# dp_tsc-v21.net
KiCad netlist of a schematic drawn in EAGLE
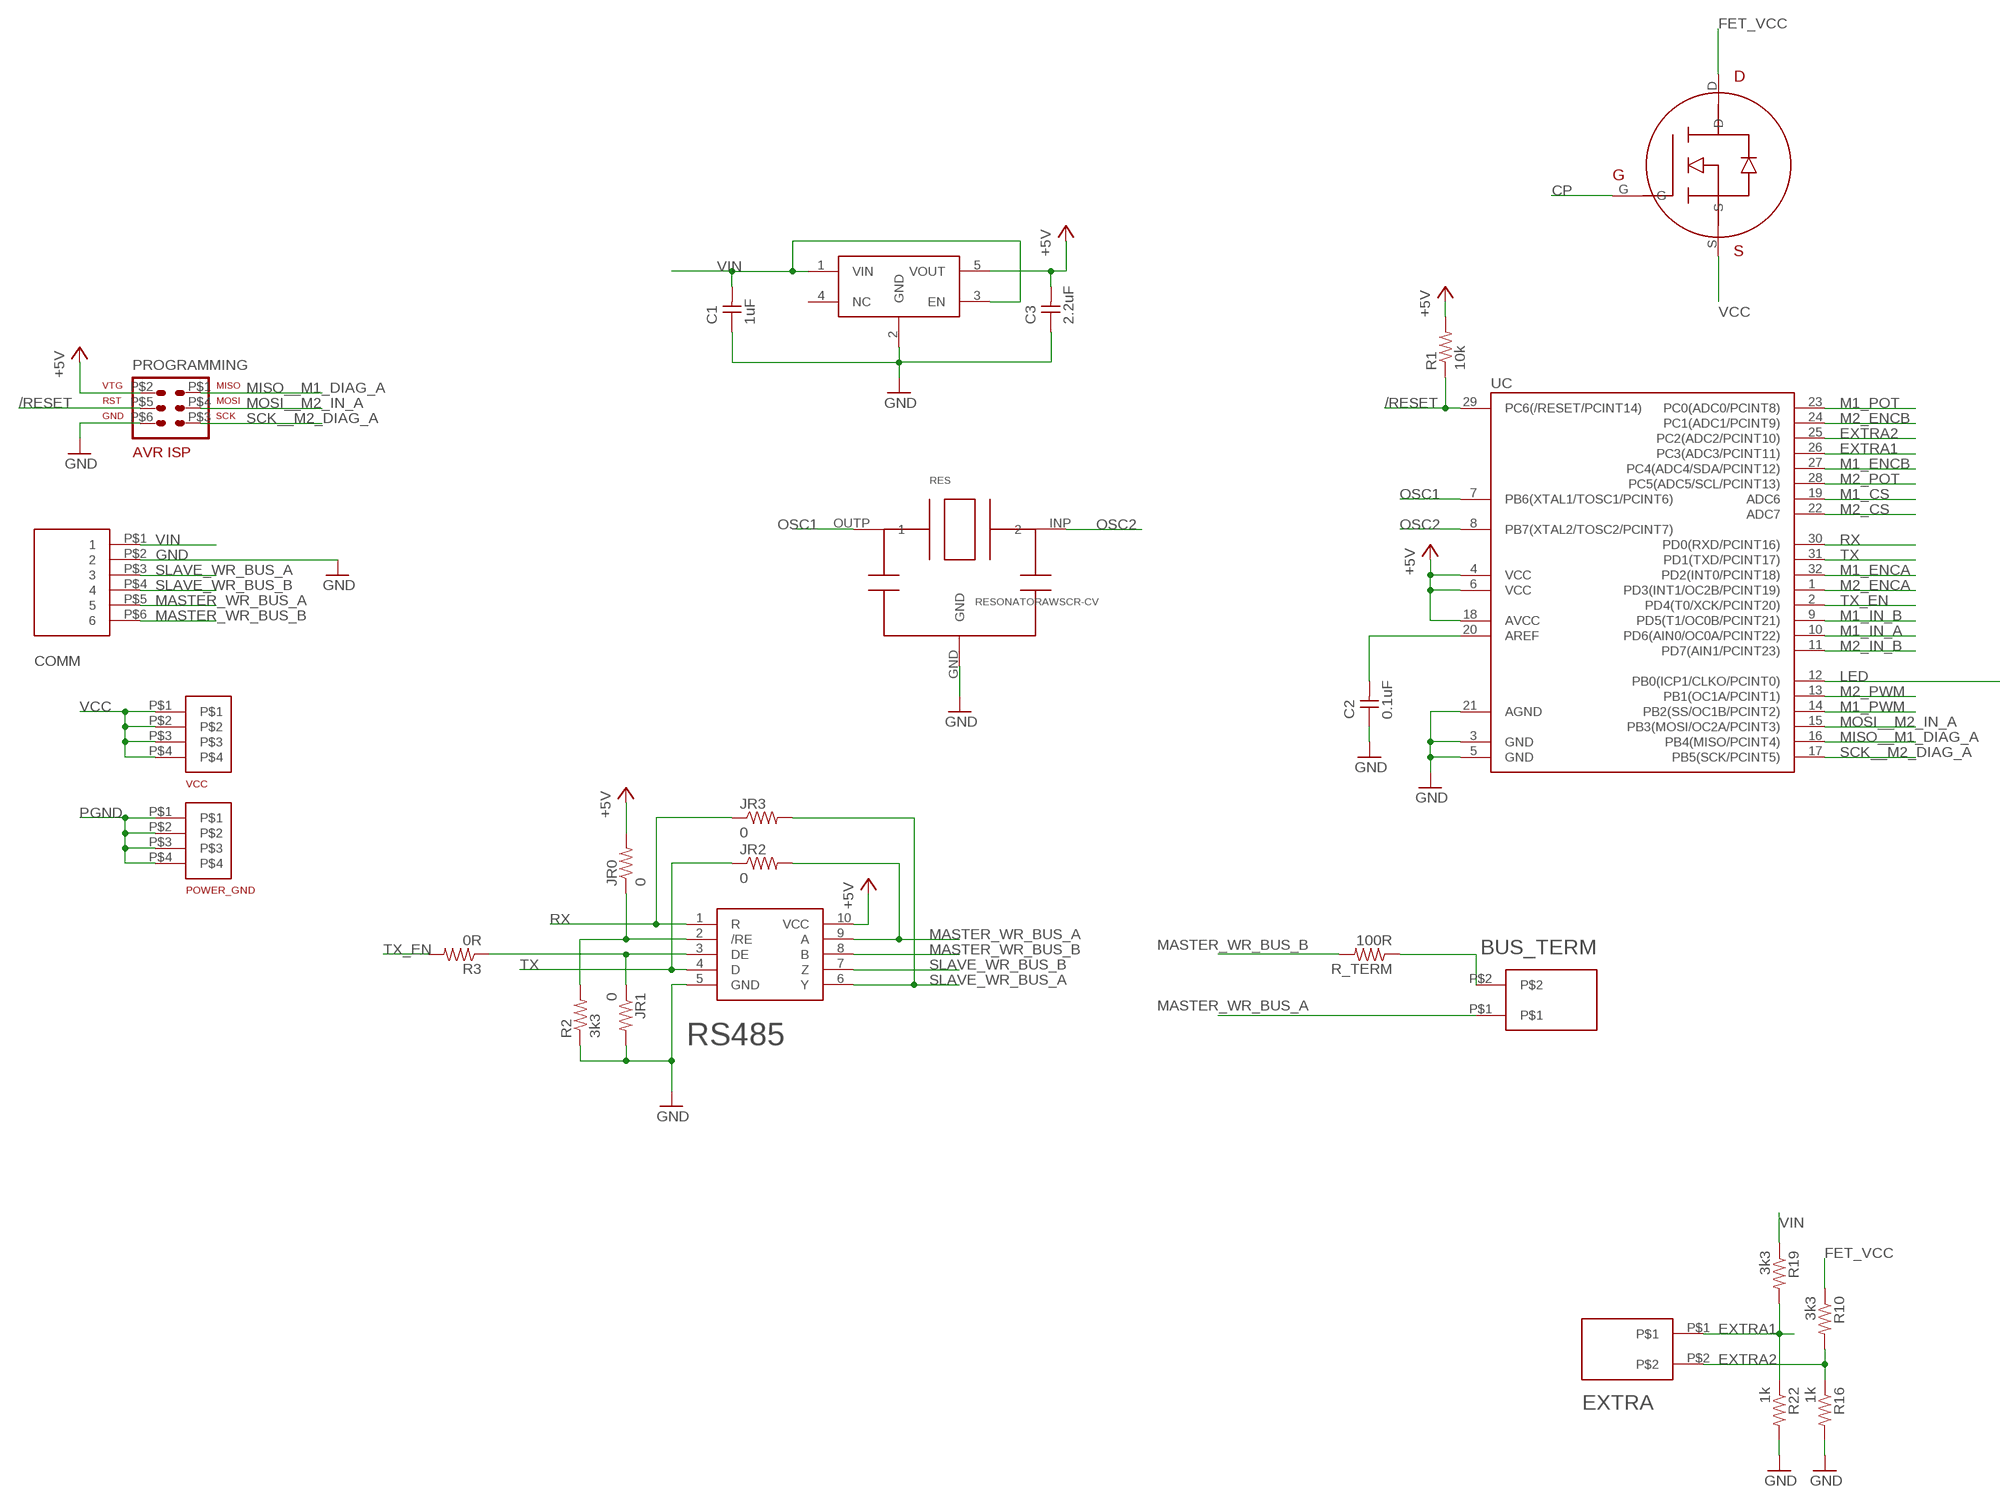
[diagram p0: schematic, sheet 1, part 1 of 2]
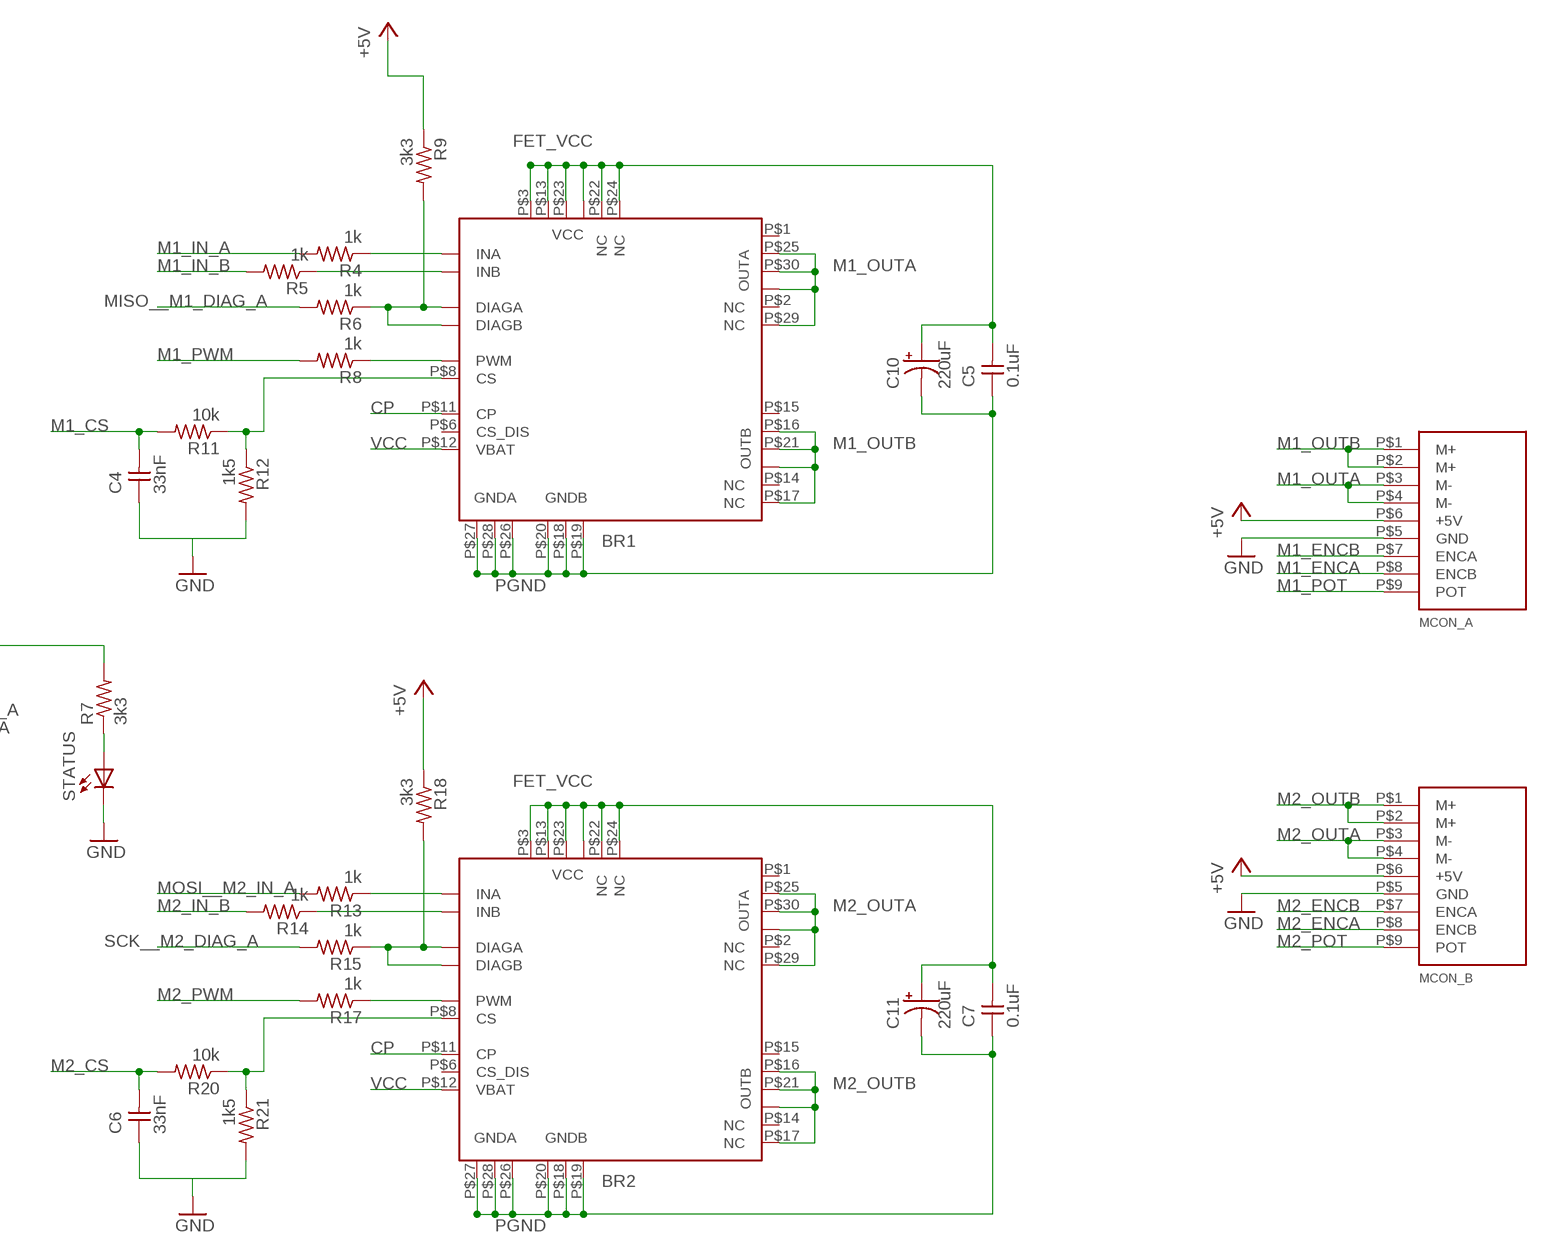
[diagram p1: schematic, sheet 1, part 2 of 2]

(export (version "E")
  (design (tool "Eeschema 10.0.6"))
  (components
    (comp (ref "BR1")
      (value "VNH5019A-E")
      (footprint "eagle-import:MULTIPOWERSO-30-SIGGI")
      (libsource (lib "eagle-import") (part "VNH5019A-E"))
    )
    (comp (ref "BR2")
      (value "VNH5019A-E")
      (footprint "eagle-import:MULTIPOWERSO-30-SIGGI")
      (libsource (lib "eagle-import") (part "VNH5019A-E"))
    )
    (comp (ref "BUS_TERM")
      (value "2PIN-100MILL")
      (footprint "eagle-import:2-PIN-100MIL")
      (libsource (lib "eagle-import") (part "2PIN-100MILL"))
    )
    (comp (ref "C1")
      (value "1uF")
      (footprint "eagle-import:0603")
      (libsource (lib "eagle-import") (part "CAPACITOR0603"))
    )
    (comp (ref "C2")
      (value "0.1uF")
      (footprint "eagle-import:0603")
      (libsource (lib "eagle-import") (part "CAPACITOR0603"))
    )
    (comp (ref "C3")
      (value "2.2uF")
      (footprint "eagle-import:0603")
      (libsource (lib "eagle-import") (part "CAPACITOR0603"))
    )
    (comp (ref "C4")
      (value "33nF")
      (footprint "eagle-import:0603")
      (libsource (lib "eagle-import") (part "CAPACITOR0603"))
    )
    (comp (ref "C5")
      (value "0.1uF")
      (footprint "eagle-import:0603")
      (libsource (lib "eagle-import") (part "CAPACITOR0603"))
    )
    (comp (ref "C6")
      (value "33nF")
      (footprint "eagle-import:0603")
      (libsource (lib "eagle-import") (part "CAPACITOR0603"))
    )
    (comp (ref "C7")
      (value "0.1uF")
      (footprint "eagle-import:0603")
      (libsource (lib "eagle-import") (part "CAPACITOR0603"))
    )
    (comp (ref "C10")
      (value "220uF")
      (footprint "eagle-import:HAO")
      (libsource (lib "eagle-import") (part "CAP-EMVY350ADA221MHA0G"))
    )
    (comp (ref "C11")
      (value "220uF")
      (footprint "eagle-import:HAO")
      (libsource (lib "eagle-import") (part "CAP-EMVY350ADA221MHA0G"))
    )
    (comp (ref "COMM")
      (value "6PIN-RIBBONCABLE-BOARDHEADER")
      (footprint "eagle-import:6PIN-HEADER-DUALROW")
      (libsource (lib "eagle-import") (part "6PIN-RIBBONCABLE-BOARDHEADER"))
    )
    (comp (ref "EXTRA")
      (value "2PIN-100MILL")
      (footprint "eagle-import:2-PIN-100MIL")
      (libsource (lib "eagle-import") (part "2PIN-100MILL"))
    )
    (comp (ref "FET")
      (value "MOSFET-N-FDD8896")
      (footprint "eagle-import:TO-252")
      (libsource (lib "eagle-import") (part "MOSFET-N-FDD8896"))
    )
    (comp (ref "JR0")
      (value "0")
      (footprint "eagle-import:0603")
      (libsource (lib "eagle-import") (part "RESISTOR0603"))
    )
    (comp (ref "JR1")
      (value "0")
      (footprint "eagle-import:0603")
      (libsource (lib "eagle-import") (part "RESISTOR0603"))
    )
    (comp (ref "JR2")
      (value "0")
      (footprint "eagle-import:0603")
      (libsource (lib "eagle-import") (part "RESISTOR0603"))
    )
    (comp (ref "JR3")
      (value "0")
      (footprint "eagle-import:0603")
      (libsource (lib "eagle-import") (part "RESISTOR0603"))
    )
    (comp (ref "MCON_A")
      (value "9-PIN-MOTOR_CONNECTOR")
      (footprint "eagle-import:9-PIN-2.54MM-TERMINAL-BLOCK")
      (libsource (lib "eagle-import") (part "9-PIN-MOTOR_CONNECTOR"))
    )
    (comp (ref "MCON_B")
      (value "9-PIN-MOTOR_CONNECTOR")
      (footprint "eagle-import:9-PIN-2.54MM-TERMINAL-BLOCK")
      (libsource (lib "eagle-import") (part "9-PIN-MOTOR_CONNECTOR"))
    )
    (comp (ref "POWER_GND")
      (value "SCREW_TERMINAL_7700K")
      (footprint "eagle-import:SCREW_TERM_7700K")
      (libsource (lib "eagle-import") (part "SCREW_TERMINAL_7700K"))
    )
    (comp (ref "PROGRAMMING")
      (value "AVR-ISP-6SURFACE_MOUNT")
      (footprint "eagle-import:SMD6")
      (libsource (lib "eagle-import") (part "AVR-ISP-6SURFACE_MOUNT"))
    )
    (comp (ref "R1")
      (value "10k")
      (footprint "eagle-import:0603")
      (libsource (lib "eagle-import") (part "RESISTOR0603"))
    )
    (comp (ref "R2")
      (value "3k3")
      (footprint "eagle-import:0603")
      (libsource (lib "eagle-import") (part "RESISTOR0603"))
    )
    (comp (ref "R3")
      (value "0R")
      (footprint "eagle-import:0603")
      (libsource (lib "eagle-import") (part "RESISTOR0603"))
    )
    (comp (ref "R4")
      (value "1k")
      (footprint "eagle-import:0603")
      (libsource (lib "eagle-import") (part "RESISTOR0603"))
    )
    (comp (ref "R5")
      (value "1k")
      (footprint "eagle-import:0603")
      (libsource (lib "eagle-import") (part "RESISTOR0603"))
    )
    (comp (ref "R6")
      (value "1k")
      (footprint "eagle-import:0603")
      (libsource (lib "eagle-import") (part "RESISTOR0603"))
    )
    (comp (ref "R7")
      (value "3k3")
      (footprint "eagle-import:0603")
      (libsource (lib "eagle-import") (part "RESISTOR0603"))
    )
    (comp (ref "R8")
      (value "1k")
      (footprint "eagle-import:0603")
      (libsource (lib "eagle-import") (part "RESISTOR0603"))
    )
    (comp (ref "R9")
      (value "3k3")
      (footprint "eagle-import:0603")
      (libsource (lib "eagle-import") (part "RESISTOR0603"))
    )
    (comp (ref "R10")
      (value "3k3")
      (footprint "eagle-import:0603")
      (libsource (lib "eagle-import") (part "RESISTOR0603"))
    )
    (comp (ref "R11")
      (value "10k")
      (footprint "eagle-import:0603")
      (libsource (lib "eagle-import") (part "RESISTOR0603"))
    )
    (comp (ref "R12")
      (value "1k5")
      (footprint "eagle-import:0603")
      (libsource (lib "eagle-import") (part "RESISTOR0603"))
    )
    (comp (ref "R13")
      (value "1k")
      (footprint "eagle-import:0603")
      (libsource (lib "eagle-import") (part "RESISTOR0603"))
    )
    (comp (ref "R14")
      (value "1k")
      (footprint "eagle-import:0603")
      (libsource (lib "eagle-import") (part "RESISTOR0603"))
    )
    (comp (ref "R15")
      (value "1k")
      (footprint "eagle-import:0603")
      (libsource (lib "eagle-import") (part "RESISTOR0603"))
    )
    (comp (ref "R16")
      (value "1k")
      (footprint "eagle-import:0603")
      (libsource (lib "eagle-import") (part "RESISTOR0603"))
    )
    (comp (ref "R17")
      (value "1k")
      (footprint "eagle-import:0603")
      (libsource (lib "eagle-import") (part "RESISTOR0603"))
    )
    (comp (ref "R18")
      (value "3k3")
      (footprint "eagle-import:0603")
      (libsource (lib "eagle-import") (part "RESISTOR0603"))
    )
    (comp (ref "R19")
      (value "3k3")
      (footprint "eagle-import:0603")
      (libsource (lib "eagle-import") (part "RESISTOR0603"))
    )
    (comp (ref "R20")
      (value "10k")
      (footprint "eagle-import:0603")
      (libsource (lib "eagle-import") (part "RESISTOR0603"))
    )
    (comp (ref "R21")
      (value "1k5")
      (footprint "eagle-import:0603")
      (libsource (lib "eagle-import") (part "RESISTOR0603"))
    )
    (comp (ref "R22")
      (value "1k")
      (footprint "eagle-import:0603")
      (libsource (lib "eagle-import") (part "RESISTOR0603"))
    )
    (comp (ref "RES")
      (value "RESONATORAWSCR-CV")
      (footprint "eagle-import:AWSCR-CV")
      (libsource (lib "eagle-import") (part "RESONATORAWSCR-CV"))
    )
    (comp (ref "RS485")
      (value "RS485-SN65HVD3086EDGSR")
      (footprint "eagle-import:MSOP-10")
      (libsource (lib "eagle-import") (part "RS485-SN65HVD3086EDGSR"))
    )
    (comp (ref "R_TERM")
      (value "100R")
      (footprint "eagle-import:0603")
      (libsource (lib "eagle-import") (part "RESISTOR0603"))
    )
    (comp (ref "STATUS")
      (value "LED1206")
      (footprint "eagle-import:CHIPLED_1206")
      (libsource (lib "eagle-import") (part "LED1206"))
    )
    (comp (ref "UC")
      (value "MEGA48/88/168-AU")
      (footprint "eagle-import:TQFP32-08")
      (libsource (lib "eagle-import") (part "MEGA48/88/168-AU"))
    )
    (comp (ref "VCC")
      (value "SCREW_TERMINAL_7700K")
      (footprint "eagle-import:SCREW_TERM_7700K")
      (libsource (lib "eagle-import") (part "SCREW_TERMINAL_7700K"))
    )
    (comp (ref "VREG")
      (value "MIC5235")
      (footprint "eagle-import:SOT-23-5")
      (libsource (lib "eagle-import") (part "MIC5235"))
    )
  )
  (nets
    (net (code "1") (name "+5V") (class "Default")
      (node (ref "C3") (pin "2") (pinfunction "2_2") (pintype "passive"))
      (node (ref "JR0") (pin "2") (pinfunction "2_2") (pintype "passive"))
      (node (ref "MCON_A") (pin "P$6") (pinfunction "+5V_P$6") (pintype "bidirectional"))
      (node (ref "MCON_B") (pin "P$6") (pinfunction "+5V_P$6") (pintype "bidirectional"))
      (node (ref "PROGRAMMING") (pin "P$2") (pinfunction "2_P$2") (pintype "passive"))
      (node (ref "R1") (pin "2") (pinfunction "2_2") (pintype "passive"))
      (node (ref "R18") (pin "1") (pinfunction "1_1") (pintype "passive"))
      (node (ref "R9") (pin "1") (pinfunction "1_1") (pintype "passive"))
      (node (ref "RS485") (pin "10") (pinfunction "VCC_10") (pintype "bidirectional"))
      (node (ref "UC") (pin "18") (pinfunction "AVCC_18") (pintype "passive"))
      (node (ref "UC") (pin "4") (pinfunction "VCC_4") (pintype "power_in"))
      (node (ref "UC") (pin "6") (pinfunction "VCC_6") (pintype "power_in"))
      (node (ref "VREG") (pin "5") (pinfunction "VOUT_5") (pintype "bidirectional"))
    )
    (net (code "2") (name "/CP") (class "Default")
      (node (ref "BR1") (pin "P$11") (pinfunction "CP_P$11") (pintype "bidirectional"))
      (node (ref "BR2") (pin "P$11") (pinfunction "CP_P$11") (pintype "bidirectional"))
      (node (ref "FET") (pin "G") (pinfunction "G_G") (pintype "bidirectional"))
    )
    (net (code "3") (name "/EXTRA1") (class "Default")
      (node (ref "EXTRA") (pin "P$1") (pinfunction "P$1_P$1") (pintype "bidirectional"))
      (node (ref "R19") (pin "2") (pinfunction "2_2") (pintype "passive"))
      (node (ref "R22") (pin "1") (pinfunction "1_1") (pintype "passive"))
      (node (ref "UC") (pin "26") (pinfunction "PC3(ADC3/PCINT11)_26") (pintype "bidirectional"))
    )
    (net (code "4") (name "/EXTRA2") (class "Default")
      (node (ref "EXTRA") (pin "P$2") (pinfunction "P$2_P$2") (pintype "bidirectional"))
      (node (ref "R10") (pin "2") (pinfunction "2_2") (pintype "passive"))
      (node (ref "R16") (pin "1") (pinfunction "1_1") (pintype "passive"))
      (node (ref "UC") (pin "25") (pinfunction "PC2(ADC2/PCINT10)_25") (pintype "bidirectional"))
    )
    (net (code "5") (name "/FET_VCC") (class "Default")
      (node (ref "BR1") (pin "P$13") (pinfunction "VCC_P$13") (pintype "power_in"))
      (node (ref "BR1") (pin "P$22") (pinfunction "NC_P$22") (pintype "bidirectional"))
      (node (ref "BR1") (pin "P$23") (pinfunction "VCC_P$23") (pintype "power_in"))
      (node (ref "BR1") (pin "P$24") (pinfunction "NC_P$24") (pintype "bidirectional"))
      (node (ref "BR1") (pin "P$3") (pinfunction "VCC_P$3") (pintype "power_in"))
      (node (ref "BR1") (pin "VCC_SLUG") (pinfunction "VCC_VCC_SLUG") (pintype "power_in"))
      (node (ref "BR2") (pin "P$13") (pinfunction "VCC_P$13") (pintype "power_in"))
      (node (ref "BR2") (pin "P$22") (pinfunction "NC_P$22") (pintype "bidirectional"))
      (node (ref "BR2") (pin "P$23") (pinfunction "VCC_P$23") (pintype "power_in"))
      (node (ref "BR2") (pin "P$24") (pinfunction "NC_P$24") (pintype "bidirectional"))
      (node (ref "BR2") (pin "P$3") (pinfunction "VCC_P$3") (pintype "power_in"))
      (node (ref "BR2") (pin "VCC_SLUG") (pinfunction "VCC_VCC_SLUG") (pintype "power_in"))
      (node (ref "C10") (pin "+") (pinfunction "+_+") (pintype "passive"))
      (node (ref "C11") (pin "+") (pinfunction "+_+") (pintype "passive"))
      (node (ref "C5") (pin "2") (pinfunction "2_2") (pintype "passive"))
      (node (ref "C7") (pin "2") (pinfunction "2_2") (pintype "passive"))
      (node (ref "FET") (pin "D") (pinfunction "D_D") (pintype "bidirectional"))
      (node (ref "R10") (pin "1") (pinfunction "1_1") (pintype "passive"))
    )
    (net (code "6") (name "/LED") (class "Default")
      (node (ref "R7") (pin "2") (pinfunction "2_2") (pintype "passive"))
      (node (ref "UC") (pin "12") (pinfunction "PB0(ICP1/CLKO/PCINT0)_12") (pintype "bidirectional"))
    )
    (net (code "7") (name "/M1_CS") (class "Default")
      (node (ref "C4") (pin "2") (pinfunction "2_2") (pintype "passive"))
      (node (ref "R11") (pin "2") (pinfunction "2_2") (pintype "passive"))
      (node (ref "UC") (pin "19") (pinfunction "ADC6_19") (pintype "passive"))
    )
    (net (code "8") (name "/M1_ENCA") (class "Default")
      (node (ref "MCON_A") (pin "P$8") (pinfunction "ENCB_P$8") (pintype "bidirectional"))
      (node (ref "UC") (pin "32") (pinfunction "PD2(INT0/PCINT18)_32") (pintype "bidirectional"))
    )
    (net (code "9") (name "/M1_ENCB") (class "Default")
      (node (ref "MCON_A") (pin "P$7") (pinfunction "ENCA_P$7") (pintype "bidirectional"))
      (node (ref "UC") (pin "27") (pinfunction "PC4(ADC4/SDA/PCINT12)_27") (pintype "bidirectional"))
    )
    (net (code "10") (name "/M1_IN_A") (class "Default")
      (node (ref "R4") (pin "2") (pinfunction "2_2") (pintype "passive"))
      (node (ref "UC") (pin "10") (pinfunction "PD6(AIN0/OC0A/PCINT22)_10") (pintype "bidirectional"))
    )
    (net (code "11") (name "/M1_IN_B") (class "Default")
      (node (ref "R5") (pin "2") (pinfunction "2_2") (pintype "passive"))
      (node (ref "UC") (pin "9") (pinfunction "PD5(T1/OC0B/PCINT21)_9") (pintype "bidirectional"))
    )
    (net (code "12") (name "/M1_OUTA") (class "Default")
      (node (ref "BR1") (pin "OUTA_SLUG") (pinfunction "OUTA_OUTA_SLUG") (pintype "passive"))
      (node (ref "BR1") (pin "P$25") (pinfunction "OUTA_P$25") (pintype "passive"))
      (node (ref "BR1") (pin "P$29") (pinfunction "NC_P$29") (pintype "bidirectional"))
      (node (ref "BR1") (pin "P$30") (pinfunction "OUTA_P$30") (pintype "passive"))
      (node (ref "MCON_A") (pin "P$3") (pinfunction "M-_P$3") (pintype "bidirectional"))
      (node (ref "MCON_A") (pin "P$4") (pinfunction "M-_P$4") (pintype "bidirectional"))
    )
    (net (code "13") (name "/M1_OUTB") (class "Default")
      (node (ref "BR1") (pin "OUTB_SLUG") (pinfunction "OUTB_OUTB_SLUG") (pintype "passive"))
      (node (ref "BR1") (pin "P$16") (pinfunction "OUTB_P$16") (pintype "passive"))
      (node (ref "BR1") (pin "P$17") (pinfunction "NC_P$17") (pintype "bidirectional"))
      (node (ref "BR1") (pin "P$21") (pinfunction "OUTB_P$21") (pintype "passive"))
      (node (ref "MCON_A") (pin "P$1") (pinfunction "M+_P$1") (pintype "bidirectional"))
      (node (ref "MCON_A") (pin "P$2") (pinfunction "M+_P$2") (pintype "bidirectional"))
    )
    (net (code "14") (name "/M1_POT") (class "Default")
      (node (ref "MCON_A") (pin "P$9") (pinfunction "POT_P$9") (pintype "bidirectional"))
      (node (ref "UC") (pin "23") (pinfunction "PC0(ADC0/PCINT8)_23") (pintype "bidirectional"))
    )
    (net (code "15") (name "/M1_PWM") (class "Default")
      (node (ref "R8") (pin "2") (pinfunction "2_2") (pintype "passive"))
      (node (ref "UC") (pin "14") (pinfunction "PB2(SS/OC1B/PCINT2)_14") (pintype "bidirectional"))
    )
    (net (code "16") (name "/M2_CS") (class "Default")
      (node (ref "C6") (pin "2") (pinfunction "2_2") (pintype "passive"))
      (node (ref "R20") (pin "2") (pinfunction "2_2") (pintype "passive"))
      (node (ref "UC") (pin "22") (pinfunction "ADC7_22") (pintype "passive"))
    )
    (net (code "17") (name "/M2_ENCA") (class "Default")
      (node (ref "MCON_B") (pin "P$8") (pinfunction "ENCB_P$8") (pintype "bidirectional"))
      (node (ref "UC") (pin "1") (pinfunction "PD3(INT1/OC2B/PCINT19)_1") (pintype "bidirectional"))
    )
    (net (code "18") (name "/M2_ENCB") (class "Default")
      (node (ref "MCON_B") (pin "P$7") (pinfunction "ENCA_P$7") (pintype "bidirectional"))
      (node (ref "UC") (pin "24") (pinfunction "PC1(ADC1/PCINT9)_24") (pintype "bidirectional"))
    )
    (net (code "19") (name "/M2_IN_B") (class "Default")
      (node (ref "R14") (pin "2") (pinfunction "2_2") (pintype "passive"))
      (node (ref "UC") (pin "11") (pinfunction "PD7(AIN1/PCINT23)_11") (pintype "bidirectional"))
    )
    (net (code "20") (name "/M2_OUTA") (class "Default")
      (node (ref "BR2") (pin "OUTA_SLUG") (pinfunction "OUTA_OUTA_SLUG") (pintype "passive"))
      (node (ref "BR2") (pin "P$25") (pinfunction "OUTA_P$25") (pintype "passive"))
      (node (ref "BR2") (pin "P$29") (pinfunction "NC_P$29") (pintype "bidirectional"))
      (node (ref "BR2") (pin "P$30") (pinfunction "OUTA_P$30") (pintype "passive"))
      (node (ref "MCON_B") (pin "P$3") (pinfunction "M-_P$3") (pintype "bidirectional"))
      (node (ref "MCON_B") (pin "P$4") (pinfunction "M-_P$4") (pintype "bidirectional"))
    )
    (net (code "21") (name "/M2_OUTB") (class "Default")
      (node (ref "BR2") (pin "OUTB_SLUG") (pinfunction "OUTB_OUTB_SLUG") (pintype "passive"))
      (node (ref "BR2") (pin "P$16") (pinfunction "OUTB_P$16") (pintype "passive"))
      (node (ref "BR2") (pin "P$17") (pinfunction "NC_P$17") (pintype "bidirectional"))
      (node (ref "BR2") (pin "P$21") (pinfunction "OUTB_P$21") (pintype "passive"))
      (node (ref "MCON_B") (pin "P$1") (pinfunction "M+_P$1") (pintype "bidirectional"))
      (node (ref "MCON_B") (pin "P$2") (pinfunction "M+_P$2") (pintype "bidirectional"))
    )
    (net (code "22") (name "/M2_POT") (class "Default")
      (node (ref "MCON_B") (pin "P$9") (pinfunction "POT_P$9") (pintype "bidirectional"))
      (node (ref "UC") (pin "28") (pinfunction "PC5(ADC5/SCL/PCINT13)_28") (pintype "bidirectional"))
    )
    (net (code "23") (name "/M2_PWM") (class "Default")
      (node (ref "R17") (pin "2") (pinfunction "2_2") (pintype "passive"))
      (node (ref "UC") (pin "13") (pinfunction "PB1(OC1A/PCINT1)_13") (pintype "bidirectional"))
    )
    (net (code "24") (name "/MASTER_WR_BUS_A") (class "Default")
      (node (ref "BUS_TERM") (pin "P$1") (pinfunction "P$1_P$1") (pintype "bidirectional"))
      (node (ref "COMM") (pin "P$5") (pinfunction "5_P$5") (pintype "bidirectional"))
      (node (ref "JR2") (pin "2") (pinfunction "2_2") (pintype "passive"))
      (node (ref "RS485") (pin "9") (pinfunction "A_9") (pintype "bidirectional"))
    )
    (net (code "25") (name "/MASTER_WR_BUS_B") (class "Default")
      (node (ref "COMM") (pin "P$6") (pinfunction "6_P$6") (pintype "bidirectional"))
      (node (ref "RS485") (pin "8") (pinfunction "B_8") (pintype "bidirectional"))
      (node (ref "R_TERM") (pin "2") (pinfunction "2_2") (pintype "passive"))
    )
    (net (code "26") (name "/MISO__M1_DIAG_A") (class "Default")
      (node (ref "PROGRAMMING") (pin "P$1") (pinfunction "1_P$1") (pintype "passive"))
      (node (ref "R6") (pin "2") (pinfunction "2_2") (pintype "passive"))
      (node (ref "UC") (pin "16") (pinfunction "PB4(MISO/PCINT4)_16") (pintype "bidirectional"))
    )
    (net (code "27") (name "/MOSI__M2_IN_A") (class "Default")
      (node (ref "PROGRAMMING") (pin "P$4") (pinfunction "4_P$4") (pintype "passive"))
      (node (ref "R13") (pin "2") (pinfunction "2_2") (pintype "passive"))
      (node (ref "UC") (pin "15") (pinfunction "PB3(MOSI/OC2A/PCINT3)_15") (pintype "bidirectional"))
    )
    (net (code "28") (name "/OSC1") (class "Default")
      (node (ref "RES") (pin "OUTP") (pinfunction "1_OUTP") (pintype "bidirectional"))
      (node (ref "UC") (pin "7") (pinfunction "PB6(XTAL1/TOSC1/PCINT6)_7") (pintype "bidirectional"))
    )
    (net (code "29") (name "/OSC2") (class "Default")
      (node (ref "RES") (pin "INP") (pinfunction "2_INP") (pintype "bidirectional"))
      (node (ref "UC") (pin "8") (pinfunction "PB7(XTAL2/TOSC2/PCINT7)_8") (pintype "bidirectional"))
    )
    (net (code "30") (name "/PGND") (class "Default")
      (node (ref "BR1") (pin "P$18") (pinfunction "GNDB_P$18") (pintype "power_in"))
      (node (ref "BR1") (pin "P$19") (pinfunction "GNDB_P$19") (pintype "power_in"))
      (node (ref "BR1") (pin "P$20") (pinfunction "GNDB_P$20") (pintype "power_in"))
      (node (ref "BR1") (pin "P$26") (pinfunction "GNDA_P$26") (pintype "power_in"))
      (node (ref "BR1") (pin "P$27") (pinfunction "GNDA_P$27") (pintype "power_in"))
      (node (ref "BR1") (pin "P$28") (pinfunction "GNDA_P$28") (pintype "power_in"))
      (node (ref "BR2") (pin "P$18") (pinfunction "GNDB_P$18") (pintype "power_in"))
      (node (ref "BR2") (pin "P$19") (pinfunction "GNDB_P$19") (pintype "power_in"))
      (node (ref "BR2") (pin "P$20") (pinfunction "GNDB_P$20") (pintype "power_in"))
      (node (ref "BR2") (pin "P$26") (pinfunction "GNDA_P$26") (pintype "power_in"))
      (node (ref "BR2") (pin "P$27") (pinfunction "GNDA_P$27") (pintype "power_in"))
      (node (ref "BR2") (pin "P$28") (pinfunction "GNDA_P$28") (pintype "power_in"))
      (node (ref "C10") (pin "-") (pinfunction "-_-") (pintype "passive"))
      (node (ref "C11") (pin "-") (pinfunction "-_-") (pintype "passive"))
      (node (ref "C5") (pin "1") (pinfunction "1_1") (pintype "passive"))
      (node (ref "C7") (pin "1") (pinfunction "1_1") (pintype "passive"))
      (node (ref "POWER_GND") (pin "P$1") (pinfunction "P$1_P$1") (pintype "bidirectional"))
      (node (ref "POWER_GND") (pin "P$2") (pinfunction "P$2_P$2") (pintype "bidirectional"))
      (node (ref "POWER_GND") (pin "P$3") (pinfunction "P$3_P$3") (pintype "bidirectional"))
      (node (ref "POWER_GND") (pin "P$4") (pinfunction "P$4_P$4") (pintype "bidirectional"))
    )
    (net (code "31") (name "/RX") (class "Default")
      (node (ref "JR3") (pin "1") (pinfunction "1_1") (pintype "passive"))
      (node (ref "RS485") (pin "1") (pinfunction "R_1") (pintype "bidirectional"))
      (node (ref "UC") (pin "30") (pinfunction "PD0(RXD/PCINT16)_30") (pintype "bidirectional"))
    )
    (net (code "32") (name "/SCK__M2_DIAG_A") (class "Default")
      (node (ref "PROGRAMMING") (pin "P$3") (pinfunction "3_P$3") (pintype "passive"))
      (node (ref "R15") (pin "2") (pinfunction "2_2") (pintype "passive"))
      (node (ref "UC") (pin "17") (pinfunction "PB5(SCK/PCINT5)_17") (pintype "bidirectional"))
    )
    (net (code "33") (name "/SLAVE_WR_BUS_A") (class "Default")
      (node (ref "COMM") (pin "P$3") (pinfunction "3_P$3") (pintype "bidirectional"))
      (node (ref "JR3") (pin "2") (pinfunction "2_2") (pintype "passive"))
      (node (ref "RS485") (pin "6") (pinfunction "Y_6") (pintype "bidirectional"))
    )
    (net (code "34") (name "/SLAVE_WR_BUS_B") (class "Default")
      (node (ref "COMM") (pin "P$4") (pinfunction "4_P$4") (pintype "bidirectional"))
      (node (ref "RS485") (pin "7") (pinfunction "Z_7") (pintype "bidirectional"))
    )
    (net (code "35") (name "/TX") (class "Default")
      (node (ref "JR2") (pin "1") (pinfunction "1_1") (pintype "passive"))
      (node (ref "RS485") (pin "4") (pinfunction "D_4") (pintype "bidirectional"))
      (node (ref "UC") (pin "31") (pinfunction "PD1(TXD/PCINT17)_31") (pintype "bidirectional"))
    )
    (net (code "36") (name "/TX_EN") (class "Default")
      (node (ref "R3") (pin "2") (pinfunction "2_2") (pintype "passive"))
      (node (ref "UC") (pin "2") (pinfunction "PD4(T0/XCK/PCINT20)_2") (pintype "bidirectional"))
    )
    (net (code "37") (name "/VCC") (class "Default")
      (node (ref "BR1") (pin "P$12") (pinfunction "VBAT_P$12") (pintype "bidirectional"))
      (node (ref "BR2") (pin "P$12") (pinfunction "VBAT_P$12") (pintype "bidirectional"))
      (node (ref "FET") (pin "S") (pinfunction "S_S") (pintype "bidirectional"))
      (node (ref "VCC") (pin "P$1") (pinfunction "P$1_P$1") (pintype "bidirectional"))
      (node (ref "VCC") (pin "P$2") (pinfunction "P$2_P$2") (pintype "bidirectional"))
      (node (ref "VCC") (pin "P$3") (pinfunction "P$3_P$3") (pintype "bidirectional"))
      (node (ref "VCC") (pin "P$4") (pinfunction "P$4_P$4") (pintype "bidirectional"))
    )
    (net (code "38") (name "/VIN") (class "Default")
      (node (ref "C1") (pin "2") (pinfunction "2_2") (pintype "passive"))
      (node (ref "COMM") (pin "P$1") (pinfunction "1_P$1") (pintype "bidirectional"))
      (node (ref "R19") (pin "1") (pinfunction "1_1") (pintype "passive"))
      (node (ref "VREG") (pin "1") (pinfunction "VIN_1") (pintype "bidirectional"))
      (node (ref "VREG") (pin "3") (pinfunction "EN_3") (pintype "bidirectional"))
    )
    (net (code "39") (name "/{slash}RESET") (class "Default")
      (node (ref "PROGRAMMING") (pin "P$5") (pinfunction "5_P$5") (pintype "passive"))
      (node (ref "R1") (pin "1") (pinfunction "1_1") (pintype "passive"))
      (node (ref "UC") (pin "29") (pinfunction "PC6(/RESET/PCINT14)_29") (pintype "bidirectional"))
    )
    (net (code "40") (name "GND") (class "Default")
      (node (ref "C1") (pin "1") (pinfunction "1_1") (pintype "passive"))
      (node (ref "C2") (pin "1") (pinfunction "1_1") (pintype "passive"))
      (node (ref "C3") (pin "1") (pinfunction "1_1") (pintype "passive"))
      (node (ref "C4") (pin "1") (pinfunction "1_1") (pintype "passive"))
      (node (ref "C6") (pin "1") (pinfunction "1_1") (pintype "passive"))
      (node (ref "COMM") (pin "P$2") (pinfunction "2_P$2") (pintype "bidirectional"))
      (node (ref "JR1") (pin "2") (pinfunction "2_2") (pintype "passive"))
      (node (ref "MCON_A") (pin "P$5") (pinfunction "GND_P$5") (pintype "bidirectional"))
      (node (ref "MCON_B") (pin "P$5") (pinfunction "GND_P$5") (pintype "bidirectional"))
      (node (ref "PROGRAMMING") (pin "P$6") (pinfunction "6_P$6") (pintype "passive"))
      (node (ref "R12") (pin "2") (pinfunction "2_2") (pintype "passive"))
      (node (ref "R16") (pin "2") (pinfunction "2_2") (pintype "passive"))
      (node (ref "R2") (pin "1") (pinfunction "1_1") (pintype "passive"))
      (node (ref "R21") (pin "2") (pinfunction "2_2") (pintype "passive"))
      (node (ref "R22") (pin "2") (pinfunction "2_2") (pintype "passive"))
      (node (ref "RES") (pin "GND") (pinfunction "GND_GND") (pintype "bidirectional"))
      (node (ref "RS485") (pin "5") (pinfunction "GND_5") (pintype "bidirectional"))
      (node (ref "STATUS") (pin "C") (pinfunction "C_C") (pintype "passive"))
      (node (ref "UC") (pin "21") (pinfunction "AGND_21") (pintype "power_in"))
      (node (ref "UC") (pin "3") (pinfunction "GND_3") (pintype "power_in"))
      (node (ref "UC") (pin "5") (pinfunction "GND_5") (pintype "power_in"))
      (node (ref "VREG") (pin "2") (pinfunction "GND_2") (pintype "bidirectional"))
    )
    (net (code "41") (name "Net-(BR1-CS)") (class "Default")
      (node (ref "BR1") (pin "P$8") (pinfunction "CS_P$8") (pintype "bidirectional"))
      (node (ref "R11") (pin "1") (pinfunction "1_1") (pintype "passive"))
      (node (ref "R12") (pin "1") (pinfunction "1_1") (pintype "passive"))
    )
    (net (code "42") (name "Net-(BR1-DIAGA)") (class "Default")
      (node (ref "BR1") (pin "P$5") (pinfunction "DIAGA_P$5") (pintype "open_collector"))
      (node (ref "BR1") (pin "P$9") (pinfunction "DIAGB_P$9") (pintype "open_collector"))
      (node (ref "R6") (pin "1") (pinfunction "1_1") (pintype "passive"))
      (node (ref "R9") (pin "2") (pinfunction "2_2") (pintype "passive"))
    )
    (net (code "43") (name "Net-(BR1-INA)") (class "Default")
      (node (ref "BR1") (pin "P$4") (pinfunction "INA_P$4") (pintype "input"))
      (node (ref "R4") (pin "1") (pinfunction "1_1") (pintype "passive"))
    )
    (net (code "44") (name "Net-(BR1-INB)") (class "Default")
      (node (ref "BR1") (pin "P$10") (pinfunction "INB_P$10") (pintype "input"))
      (node (ref "R5") (pin "1") (pinfunction "1_1") (pintype "passive"))
    )
    (net (code "45") (name "Net-(BR1-PWM)") (class "Default")
      (node (ref "BR1") (pin "P$7") (pinfunction "PWM_P$7") (pintype "input"))
      (node (ref "R8") (pin "1") (pinfunction "1_1") (pintype "passive"))
    )
    (net (code "46") (name "Net-(BR2-CS)") (class "Default")
      (node (ref "BR2") (pin "P$8") (pinfunction "CS_P$8") (pintype "bidirectional"))
      (node (ref "R20") (pin "1") (pinfunction "1_1") (pintype "passive"))
      (node (ref "R21") (pin "1") (pinfunction "1_1") (pintype "passive"))
    )
    (net (code "47") (name "Net-(BR2-DIAGA)") (class "Default")
      (node (ref "BR2") (pin "P$5") (pinfunction "DIAGA_P$5") (pintype "open_collector"))
      (node (ref "BR2") (pin "P$9") (pinfunction "DIAGB_P$9") (pintype "open_collector"))
      (node (ref "R15") (pin "1") (pinfunction "1_1") (pintype "passive"))
      (node (ref "R18") (pin "2") (pinfunction "2_2") (pintype "passive"))
    )
    (net (code "48") (name "Net-(BR2-INA)") (class "Default")
      (node (ref "BR2") (pin "P$4") (pinfunction "INA_P$4") (pintype "input"))
      (node (ref "R13") (pin "1") (pinfunction "1_1") (pintype "passive"))
    )
    (net (code "49") (name "Net-(BR2-INB)") (class "Default")
      (node (ref "BR2") (pin "P$10") (pinfunction "INB_P$10") (pintype "input"))
      (node (ref "R14") (pin "1") (pinfunction "1_1") (pintype "passive"))
    )
    (net (code "50") (name "Net-(BR2-PWM)") (class "Default")
      (node (ref "BR2") (pin "P$7") (pinfunction "PWM_P$7") (pintype "input"))
      (node (ref "R17") (pin "1") (pinfunction "1_1") (pintype "passive"))
    )
    (net (code "51") (name "Net-(BUS_TERM-PadP$2)") (class "Default")
      (node (ref "BUS_TERM") (pin "P$2") (pinfunction "P$2_P$2") (pintype "bidirectional"))
      (node (ref "R_TERM") (pin "1") (pinfunction "1_1") (pintype "passive"))
    )
    (net (code "52") (name "Net-(R7-Pad1)") (class "Default")
      (node (ref "R7") (pin "1") (pinfunction "1_1") (pintype "passive"))
      (node (ref "STATUS") (pin "A") (pinfunction "A_A") (pintype "passive"))
    )
    (net (code "53") (name "Net-(RS485-DE)") (class "Default")
      (node (ref "JR1") (pin "1") (pinfunction "1_1") (pintype "passive"))
      (node (ref "R3") (pin "1") (pinfunction "1_1") (pintype "passive"))
      (node (ref "RS485") (pin "3") (pinfunction "DE_3") (pintype "bidirectional"))
    )
    (net (code "54") (name "Net-(RS485-{slash}RE)") (class "Default")
      (node (ref "JR0") (pin "1") (pinfunction "1_1") (pintype "passive"))
      (node (ref "R2") (pin "2") (pinfunction "2_2") (pintype "passive"))
      (node (ref "RS485") (pin "2") (pinfunction "/RE_2") (pintype "bidirectional"))
    )
    (net (code "55") (name "Net-(UC-AREF)") (class "Default")
      (node (ref "C2") (pin "2") (pinfunction "2_2") (pintype "passive"))
      (node (ref "UC") (pin "20") (pinfunction "AREF_20") (pintype "passive"))
    )
    (net (code "56") (name "unconnected-(BR1-CS_DIS-PadP$6)") (class "Default")
      (node (ref "BR1") (pin "P$6") (pinfunction "CS_DIS_P$6") (pintype "bidirectional"))
    )
    (net (code "57") (name "unconnected-(BR1-NC-PadP$2)") (class "Default")
      (node (ref "BR1") (pin "P$2") (pinfunction "NC_P$2") (pintype "bidirectional"))
    )
    (net (code "58") (name "unconnected-(BR1-NC-PadP$14)") (class "Default")
      (node (ref "BR1") (pin "P$14") (pinfunction "NC_P$14") (pintype "bidirectional"))
    )
    (net (code "59") (name "unconnected-(BR1-OUTA-PadP$1)") (class "Default")
      (node (ref "BR1") (pin "P$1") (pinfunction "OUTA_P$1") (pintype "output"))
    )
    (net (code "60") (name "unconnected-(BR1-OUTB-PadP$15)") (class "Default")
      (node (ref "BR1") (pin "P$15") (pinfunction "OUTB_P$15") (pintype "output"))
    )
    (net (code "61") (name "unconnected-(BR2-CS_DIS-PadP$6)") (class "Default")
      (node (ref "BR2") (pin "P$6") (pinfunction "CS_DIS_P$6") (pintype "bidirectional"))
    )
    (net (code "62") (name "unconnected-(BR2-NC-PadP$2)") (class "Default")
      (node (ref "BR2") (pin "P$2") (pinfunction "NC_P$2") (pintype "bidirectional"))
    )
    (net (code "63") (name "unconnected-(BR2-NC-PadP$14)") (class "Default")
      (node (ref "BR2") (pin "P$14") (pinfunction "NC_P$14") (pintype "bidirectional"))
    )
    (net (code "64") (name "unconnected-(BR2-OUTA-PadP$1)") (class "Default")
      (node (ref "BR2") (pin "P$1") (pinfunction "OUTA_P$1") (pintype "output"))
    )
    (net (code "65") (name "unconnected-(BR2-OUTB-PadP$15)") (class "Default")
      (node (ref "BR2") (pin "P$15") (pinfunction "OUTB_P$15") (pintype "output"))
    )
    (net (code "66") (name "unconnected-(VREG-NC-Pad4)") (class "Default")
      (node (ref "VREG") (pin "4") (pinfunction "NC_4") (pintype "bidirectional"))
    )
  )
)
